# ETH-IO_RS485-DS18B20-Panel.net
KiCad netlist of a schematic drawn in EAGLE
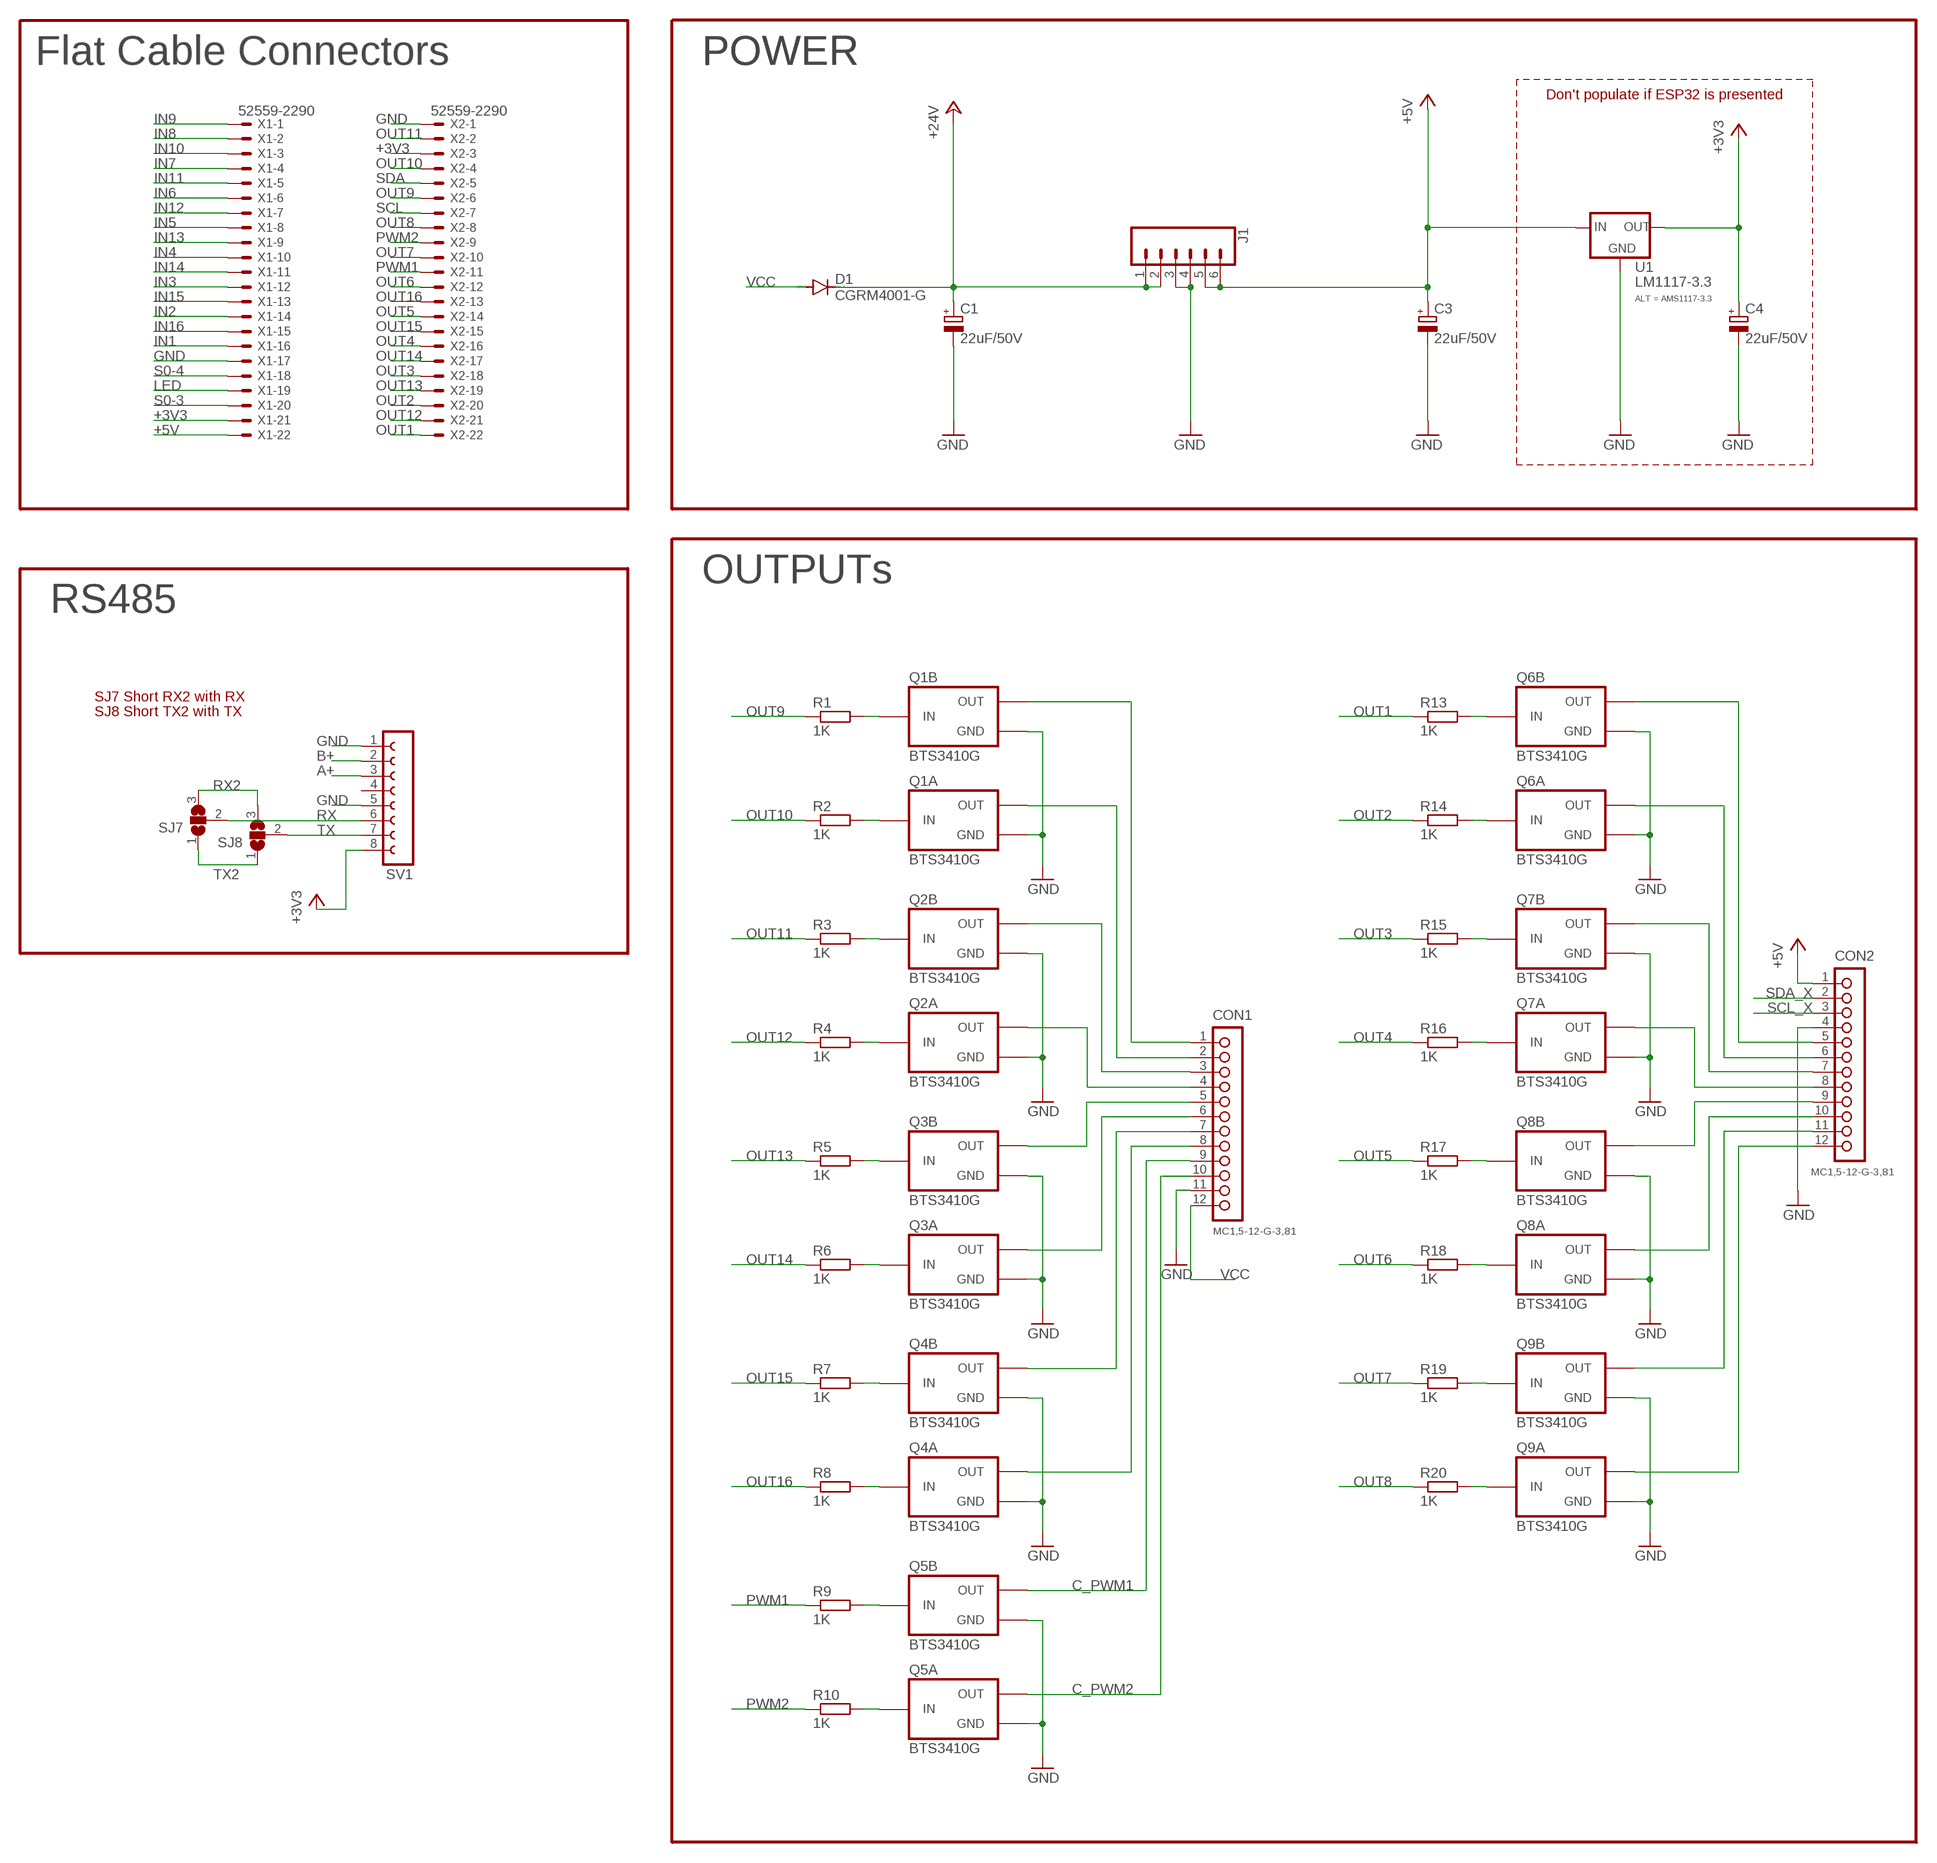
[diagram p0: schematic, sheet 1, part 1 of 2]
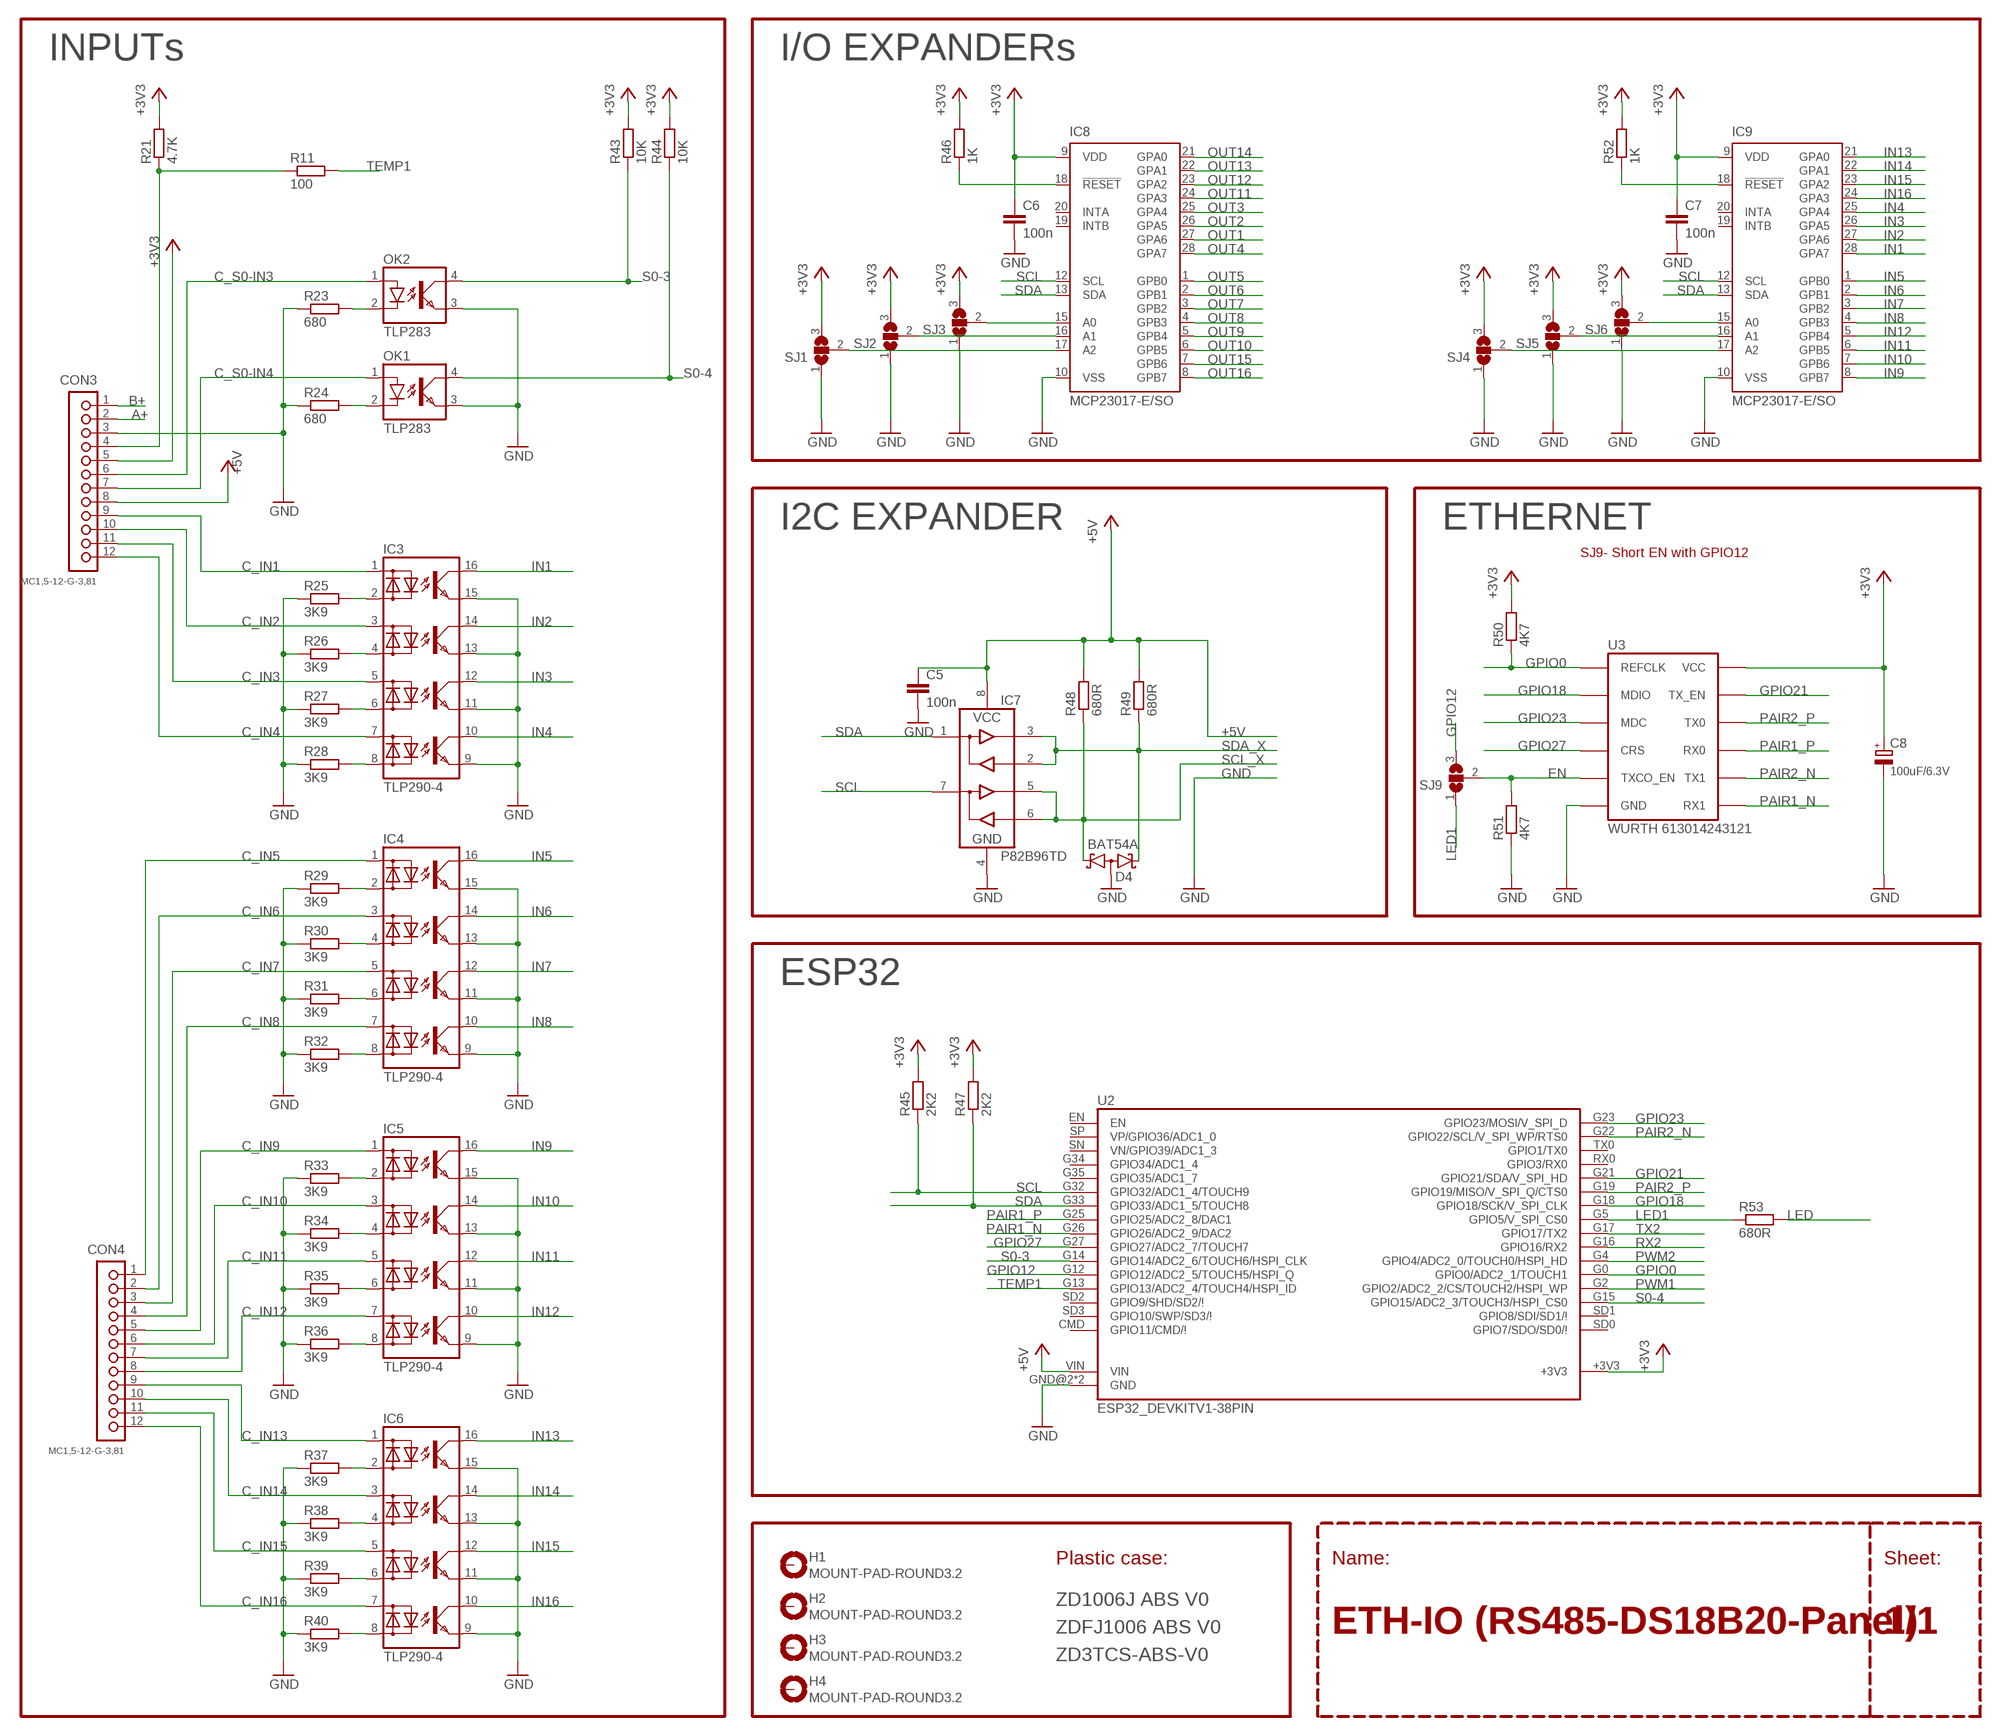
[diagram p1: schematic, sheet 1, part 2 of 2]

(export (version "E")
  (design (tool "Eeschema 10.0.6"))
  (components
    (comp (ref "C1")
      (value "22uF/50V")
      (footprint "eagle-import:PANASONIC_C")
      (libsource (lib "eagle-import") (part "CPOL-EUC"))
    )
    (comp (ref "C3")
      (value "22uF/50V")
      (footprint "eagle-import:PANASONIC_C")
      (libsource (lib "eagle-import") (part "CPOL-EUC"))
    )
    (comp (ref "C4")
      (value "22uF/50V")
      (footprint "eagle-import:PANASONIC_C")
      (libsource (lib "eagle-import") (part "CPOL-EUC"))
    )
    (comp (ref "C5")
      (value "100n")
      (footprint "eagle-import:C0805")
      (libsource (lib "eagle-import") (part "C-EUC0805"))
    )
    (comp (ref "C6")
      (value "100n")
      (footprint "eagle-import:C0805")
      (libsource (lib "eagle-import") (part "C-EUC0805"))
    )
    (comp (ref "C7")
      (value "100n")
      (footprint "eagle-import:C0805")
      (libsource (lib "eagle-import") (part "C-EUC0805"))
    )
    (comp (ref "C8")
      (value "100uF/6.3V")
      (footprint "eagle-import:PANASONIC_C")
      (libsource (lib "eagle-import") (part "CPOL-EUC"))
    )
    (comp (ref "CON1")
      (value "MC1,5-12-G-3,81")
      (footprint "eagle-import:MC1,5_12-G-3,81")
      (libsource (lib "eagle-import") (part "MC1,5-12-G-?3,81"))
    )
    (comp (ref "CON2")
      (value "MC1,5-12-G-3,81")
      (footprint "eagle-import:MC1,5_12-G-3,81")
      (libsource (lib "eagle-import") (part "MC1,5-12-G-?3,81"))
    )
    (comp (ref "CON3")
      (value "MC1,5-12-G-3,81")
      (footprint "eagle-import:MC1,5_12-G-3,81")
      (libsource (lib "eagle-import") (part "MC1,5-12-G-?3,81"))
    )
    (comp (ref "CON4")
      (value "MC1,5-12-G-3,81")
      (footprint "eagle-import:MC1,5_12-G-3,81")
      (libsource (lib "eagle-import") (part "MC1,5-12-G-?3,81"))
    )
    (comp (ref "D1")
      (value "CGRM4001-G")
      (footprint "eagle-import:SOD-123_MINI-SMA")
      (libsource (lib "eagle-import") (part "CGRM400-G1"))
    )
    (comp (ref "D4")
      (value "BAT54A")
      (footprint "eagle-import:SOT23")
      (libsource (lib "eagle-import") (part "BAT54A"))
    )
    (comp (ref "H1")
      (value "MOUNT-PAD-ROUND3.2")
      (footprint "eagle-import:3,2-PAD")
      (libsource (lib "eagle-import") (part "MOUNT-PAD-ROUND3.2"))
    )
    (comp (ref "H2")
      (value "MOUNT-PAD-ROUND3.2")
      (footprint "eagle-import:3,2-PAD")
      (libsource (lib "eagle-import") (part "MOUNT-PAD-ROUND3.2"))
    )
    (comp (ref "H3")
      (value "MOUNT-PAD-ROUND3.2")
      (footprint "eagle-import:3,2-PAD")
      (libsource (lib "eagle-import") (part "MOUNT-PAD-ROUND3.2"))
    )
    (comp (ref "H4")
      (value "MOUNT-PAD-ROUND3.2")
      (footprint "eagle-import:3,2-PAD")
      (libsource (lib "eagle-import") (part "MOUNT-PAD-ROUND3.2"))
    )
    (comp (ref "IC3")
      (value "TLP290-4")
      (footprint "eagle-import:SO16")
      (libsource (lib "eagle-import") (part "TLP290-4"))
    )
    (comp (ref "IC4")
      (value "TLP290-4")
      (footprint "eagle-import:SO16")
      (libsource (lib "eagle-import") (part "TLP290-4"))
    )
    (comp (ref "IC5")
      (value "TLP290-4")
      (footprint "eagle-import:SO16")
      (libsource (lib "eagle-import") (part "TLP290-4"))
    )
    (comp (ref "IC6")
      (value "TLP290-4")
      (footprint "eagle-import:SO16")
      (libsource (lib "eagle-import") (part "TLP290-4"))
    )
    (comp (ref "IC7")
      (value "P82B96TD")
      (footprint "eagle-import:SO08")
      (libsource (lib "eagle-import") (part "P82B96?TD"))
    )
    (comp (ref "IC8")
      (value "MCP23017-E/SO")
      (footprint "eagle-import:SO28W")
      (fields (field (name "MF") "MICROCHIP"))
      (libsource (lib "eagle-import") (part "MCP23017SO"))
    )
    (comp (ref "IC9")
      (value "MCP23017-E/SO")
      (footprint "eagle-import:SO28W")
      (fields (field (name "MF") "MICROCHIP"))
      (libsource (lib "eagle-import") (part "MCP23017SO"))
    )
    (comp (ref "J1")
      (value "CONN_06NO_SILK_FEMALE_PTH")
      (footprint "eagle-import:1X06_NO_SILK")
      (libsource (lib "eagle-import") (part "CONN_06NO_SILK_FEMALE_PTH"))
    )
    (comp (ref "OK1")
      (value "TLP283")
      (footprint "eagle-import:MINI-FLAT-4")
      (libsource (lib "eagle-import") (part "TLP283"))
    )
    (comp (ref "OK2")
      (value "TLP283")
      (footprint "eagle-import:MINI-FLAT-4")
      (libsource (lib "eagle-import") (part "TLP283"))
    )
    (comp (ref "Q1")
      (value "BTS3410G")
      (footprint "eagle-import:SO8")
      (libsource (lib "eagle-import") (part "BTS3410G"))
    )
    (comp (ref "Q2")
      (value "BTS3410G")
      (footprint "eagle-import:SO8")
      (libsource (lib "eagle-import") (part "BTS3410G"))
    )
    (comp (ref "Q3")
      (value "BTS3410G")
      (footprint "eagle-import:SO8")
      (libsource (lib "eagle-import") (part "BTS3410G"))
    )
    (comp (ref "Q4")
      (value "BTS3410G")
      (footprint "eagle-import:SO8")
      (libsource (lib "eagle-import") (part "BTS3410G"))
    )
    (comp (ref "Q5")
      (value "BTS3410G")
      (footprint "eagle-import:SO8")
      (libsource (lib "eagle-import") (part "BTS3410G"))
    )
    (comp (ref "Q6")
      (value "BTS3410G")
      (footprint "eagle-import:SO8")
      (libsource (lib "eagle-import") (part "BTS3410G"))
    )
    (comp (ref "Q7")
      (value "BTS3410G")
      (footprint "eagle-import:SO8")
      (libsource (lib "eagle-import") (part "BTS3410G"))
    )
    (comp (ref "Q8")
      (value "BTS3410G")
      (footprint "eagle-import:SO8")
      (libsource (lib "eagle-import") (part "BTS3410G"))
    )
    (comp (ref "Q9")
      (value "BTS3410G")
      (footprint "eagle-import:SO8")
      (libsource (lib "eagle-import") (part "BTS3410G"))
    )
    (comp (ref "R1")
      (value "1K")
      (footprint "eagle-import:R0805")
      (libsource (lib "eagle-import") (part "R-EU_R0805"))
    )
    (comp (ref "R2")
      (value "1K")
      (footprint "eagle-import:R0805")
      (libsource (lib "eagle-import") (part "R-EU_R0805"))
    )
    (comp (ref "R3")
      (value "1K")
      (footprint "eagle-import:R0805")
      (libsource (lib "eagle-import") (part "R-EU_R0805"))
    )
    (comp (ref "R4")
      (value "1K")
      (footprint "eagle-import:R0805")
      (libsource (lib "eagle-import") (part "R-EU_R0805"))
    )
    (comp (ref "R5")
      (value "1K")
      (footprint "eagle-import:R0805")
      (libsource (lib "eagle-import") (part "R-EU_R0805"))
    )
    (comp (ref "R6")
      (value "1K")
      (footprint "eagle-import:R0805")
      (libsource (lib "eagle-import") (part "R-EU_R0805"))
    )
    (comp (ref "R7")
      (value "1K")
      (footprint "eagle-import:R0805")
      (libsource (lib "eagle-import") (part "R-EU_R0805"))
    )
    (comp (ref "R8")
      (value "1K")
      (footprint "eagle-import:R0805")
      (libsource (lib "eagle-import") (part "R-EU_R0805"))
    )
    (comp (ref "R9")
      (value "1K")
      (footprint "eagle-import:R0805")
      (libsource (lib "eagle-import") (part "R-EU_R0805"))
    )
    (comp (ref "R10")
      (value "1K")
      (footprint "eagle-import:R0805")
      (libsource (lib "eagle-import") (part "R-EU_R0805"))
    )
    (comp (ref "R11")
      (value "100")
      (footprint "eagle-import:R0805")
      (libsource (lib "eagle-import") (part "R-EU_R0805"))
    )
    (comp (ref "R13")
      (value "1K")
      (footprint "eagle-import:R0805")
      (libsource (lib "eagle-import") (part "R-EU_R0805"))
    )
    (comp (ref "R14")
      (value "1K")
      (footprint "eagle-import:R0805")
      (libsource (lib "eagle-import") (part "R-EU_R0805"))
    )
    (comp (ref "R15")
      (value "1K")
      (footprint "eagle-import:R0805")
      (libsource (lib "eagle-import") (part "R-EU_R0805"))
    )
    (comp (ref "R16")
      (value "1K")
      (footprint "eagle-import:R0805")
      (libsource (lib "eagle-import") (part "R-EU_R0805"))
    )
    (comp (ref "R17")
      (value "1K")
      (footprint "eagle-import:R0805")
      (libsource (lib "eagle-import") (part "R-EU_R0805"))
    )
    (comp (ref "R18")
      (value "1K")
      (footprint "eagle-import:R0805")
      (libsource (lib "eagle-import") (part "R-EU_R0805"))
    )
    (comp (ref "R19")
      (value "1K")
      (footprint "eagle-import:R0805")
      (libsource (lib "eagle-import") (part "R-EU_R0805"))
    )
    (comp (ref "R20")
      (value "1K")
      (footprint "eagle-import:R0805")
      (libsource (lib "eagle-import") (part "R-EU_R0805"))
    )
    (comp (ref "R21")
      (value "4.7K")
      (footprint "eagle-import:R0805")
      (libsource (lib "eagle-import") (part "R-EU_R0805"))
    )
    (comp (ref "R23")
      (value "680")
      (footprint "eagle-import:R0805")
      (libsource (lib "eagle-import") (part "R-EU_R0805"))
    )
    (comp (ref "R24")
      (value "680")
      (footprint "eagle-import:R0805")
      (libsource (lib "eagle-import") (part "R-EU_R0805"))
    )
    (comp (ref "R25")
      (value "3K9")
      (footprint "eagle-import:R0805")
      (libsource (lib "eagle-import") (part "R-EU_R0805"))
    )
    (comp (ref "R26")
      (value "3K9")
      (footprint "eagle-import:R0805")
      (libsource (lib "eagle-import") (part "R-EU_R0805"))
    )
    (comp (ref "R27")
      (value "3K9")
      (footprint "eagle-import:R0805")
      (libsource (lib "eagle-import") (part "R-EU_R0805"))
    )
    (comp (ref "R28")
      (value "3K9")
      (footprint "eagle-import:R0805")
      (libsource (lib "eagle-import") (part "R-EU_R0805"))
    )
    (comp (ref "R29")
      (value "3K9")
      (footprint "eagle-import:R0805")
      (libsource (lib "eagle-import") (part "R-EU_R0805"))
    )
    (comp (ref "R30")
      (value "3K9")
      (footprint "eagle-import:R0805")
      (libsource (lib "eagle-import") (part "R-EU_R0805"))
    )
    (comp (ref "R31")
      (value "3K9")
      (footprint "eagle-import:R0805")
      (libsource (lib "eagle-import") (part "R-EU_R0805"))
    )
    (comp (ref "R32")
      (value "3K9")
      (footprint "eagle-import:R0805")
      (libsource (lib "eagle-import") (part "R-EU_R0805"))
    )
    (comp (ref "R33")
      (value "3K9")
      (footprint "eagle-import:R0805")
      (libsource (lib "eagle-import") (part "R-EU_R0805"))
    )
    (comp (ref "R34")
      (value "3K9")
      (footprint "eagle-import:R0805")
      (libsource (lib "eagle-import") (part "R-EU_R0805"))
    )
    (comp (ref "R35")
      (value "3K9")
      (footprint "eagle-import:R0805")
      (libsource (lib "eagle-import") (part "R-EU_R0805"))
    )
    (comp (ref "R36")
      (value "3K9")
      (footprint "eagle-import:R0805")
      (libsource (lib "eagle-import") (part "R-EU_R0805"))
    )
    (comp (ref "R37")
      (value "3K9")
      (footprint "eagle-import:R0805")
      (libsource (lib "eagle-import") (part "R-EU_R0805"))
    )
    (comp (ref "R38")
      (value "3K9")
      (footprint "eagle-import:R0805")
      (libsource (lib "eagle-import") (part "R-EU_R0805"))
    )
    (comp (ref "R39")
      (value "3K9")
      (footprint "eagle-import:R0805")
      (libsource (lib "eagle-import") (part "R-EU_R0805"))
    )
    (comp (ref "R40")
      (value "3K9")
      (footprint "eagle-import:R0805")
      (libsource (lib "eagle-import") (part "R-EU_R0805"))
    )
    (comp (ref "R43")
      (value "10K")
      (footprint "eagle-import:R0805")
      (libsource (lib "eagle-import") (part "R-EU_R0805"))
    )
    (comp (ref "R44")
      (value "10K")
      (footprint "eagle-import:R0805")
      (libsource (lib "eagle-import") (part "R-EU_R0805"))
    )
    (comp (ref "R45")
      (value "2K2")
      (footprint "eagle-import:R0805")
      (libsource (lib "eagle-import") (part "R-EU_R0805"))
    )
    (comp (ref "R46")
      (value "1K")
      (footprint "eagle-import:R0805")
      (libsource (lib "eagle-import") (part "R-EU_R0805"))
    )
    (comp (ref "R47")
      (value "2K2")
      (footprint "eagle-import:R0805")
      (libsource (lib "eagle-import") (part "R-EU_R0805"))
    )
    (comp (ref "R48")
      (value "680R")
      (footprint "eagle-import:R0805")
      (libsource (lib "eagle-import") (part "R-EU_R0805"))
    )
    (comp (ref "R49")
      (value "680R")
      (footprint "eagle-import:R0805")
      (libsource (lib "eagle-import") (part "R-EU_R0805"))
    )
    (comp (ref "R50")
      (value "4K7")
      (footprint "eagle-import:R0805")
      (libsource (lib "eagle-import") (part "R-EU_R0805"))
    )
    (comp (ref "R51")
      (value "4K7")
      (footprint "eagle-import:R0805")
      (libsource (lib "eagle-import") (part "R-EU_R0805"))
    )
    (comp (ref "R52")
      (value "1K")
      (footprint "eagle-import:R0805")
      (libsource (lib "eagle-import") (part "R-EU_R0805"))
    )
    (comp (ref "R53")
      (value "680R")
      (footprint "eagle-import:R0805")
      (libsource (lib "eagle-import") (part "R-EU_R0805"))
    )
    (comp (ref "SJ1")
      (value "SJ2W")
      (footprint "eagle-import:SJ_2")
      (libsource (lib "eagle-import") (part "SJ2W"))
    )
    (comp (ref "SJ2")
      (value "SJ2W")
      (footprint "eagle-import:SJ_2")
      (libsource (lib "eagle-import") (part "SJ2W"))
    )
    (comp (ref "SJ3")
      (value "SJ2W")
      (footprint "eagle-import:SJ_2")
      (libsource (lib "eagle-import") (part "SJ2W"))
    )
    (comp (ref "SJ4")
      (value "SJ2W")
      (footprint "eagle-import:SJ_2")
      (libsource (lib "eagle-import") (part "SJ2W"))
    )
    (comp (ref "SJ5")
      (value "SJ2W")
      (footprint "eagle-import:SJ_2")
      (libsource (lib "eagle-import") (part "SJ2W"))
    )
    (comp (ref "SJ6")
      (value "SJ2W")
      (footprint "eagle-import:SJ_2")
      (libsource (lib "eagle-import") (part "SJ2W"))
    )
    (comp (ref "SJ7")
      (value "SJ2W")
      (footprint "eagle-import:SJ_2")
      (libsource (lib "eagle-import") (part "SJ2W"))
    )
    (comp (ref "SJ8")
      (value "SJ2W")
      (footprint "eagle-import:SJ_2")
      (libsource (lib "eagle-import") (part "SJ2W"))
    )
    (comp (ref "SJ9")
      (value "SJ2W")
      (footprint "eagle-import:SJ_2")
      (libsource (lib "eagle-import") (part "SJ2W"))
    )
    (comp (ref "SV1")
      (value "FE08-1")
      (footprint "eagle-import:FE08")
      (libsource (lib "eagle-import") (part "FE08-1"))
    )
    (comp (ref "U1")
      (value "LM1117-3.3")
      (footprint "eagle-import:SOT223")
      (fields (field (name "ALT") "AMS1117-3.3"))
      (libsource (lib "eagle-import") (part "LM1117-3.3"))
    )
    (comp (ref "U2")
      (value "ESP32_DEVKITV1-38PIN")
      (footprint "eagle-import:ESP32_DEVKITV1_38PIN")
      (libsource (lib "eagle-import") (part "ESP32_DEVKITV1-38PIN"))
    )
    (comp (ref "U3")
      (value "WURTH 613014243121")
      (footprint "eagle-import:LAN8720_ETH_BOARD")
      (libsource (lib "eagle-import") (part "LAN8720_ETH_BOARD"))
    )
    (comp (ref "X1")
      (value "52559-2290")
      (footprint "eagle-import:52559-2290")
      (fields (field (name "MF") "MOLEX"))
      (libsource (lib "eagle-import") (part "52559-2290"))
    )
    (comp (ref "X2")
      (value "52559-2290")
      (footprint "eagle-import:52559-2290")
      (fields (field (name "MF") "MOLEX"))
      (libsource (lib "eagle-import") (part "52559-2290"))
    )
  )
  (nets
    (net (code "1") (name "+3V3") (class "Default")
      (node (ref "C4") (pin "+") (pinfunction "+_+") (pintype "passive"))
      (node (ref "C6") (pin "1") (pinfunction "1_1") (pintype "passive"))
      (node (ref "C7") (pin "1") (pinfunction "1_1") (pintype "passive"))
      (node (ref "C8") (pin "+") (pinfunction "+_+") (pintype "passive"))
      (node (ref "CON3") (pin "5") (pinfunction "5_5") (pintype "passive"))
      (node (ref "IC8") (pin "9") (pinfunction "VDD_9") (pintype "power_in"))
      (node (ref "IC9") (pin "9") (pinfunction "VDD_9") (pintype "power_in"))
      (node (ref "R21") (pin "2") (pinfunction "2_2") (pintype "passive"))
      (node (ref "R43") (pin "2") (pinfunction "2_2") (pintype "passive"))
      (node (ref "R44") (pin "2") (pinfunction "2_2") (pintype "passive"))
      (node (ref "R45") (pin "2") (pinfunction "2_2") (pintype "passive"))
      (node (ref "R46") (pin "2") (pinfunction "2_2") (pintype "passive"))
      (node (ref "R47") (pin "2") (pinfunction "2_2") (pintype "passive"))
      (node (ref "R50") (pin "2") (pinfunction "2_2") (pintype "passive"))
      (node (ref "R52") (pin "2") (pinfunction "2_2") (pintype "passive"))
      (node (ref "SJ1") (pin "3") (pinfunction "3_3") (pintype "passive"))
      (node (ref "SJ2") (pin "3") (pinfunction "3_3") (pintype "passive"))
      (node (ref "SJ3") (pin "3") (pinfunction "3_3") (pintype "passive"))
      (node (ref "SJ4") (pin "3") (pinfunction "3_3") (pintype "passive"))
      (node (ref "SJ5") (pin "3") (pinfunction "3_3") (pintype "passive"))
      (node (ref "SJ6") (pin "3") (pinfunction "3_3") (pintype "passive"))
      (node (ref "SV1") (pin "8") (pinfunction "8_8") (pintype "passive"))
      (node (ref "U1") (pin "2") (pinfunction "OUT_2") (pintype "output"))
      (node (ref "U1") (pin "4") (pinfunction "OUT_4") (pintype "output"))
      (node (ref "U2") (pin "+3V3") (pinfunction "+3V3_+3V3") (pintype "power_in"))
      (node (ref "U3") (pin "VCC") (pinfunction "VCC_VCC") (pintype "power_in"))
      (node (ref "U3") (pin "VCC@1") (pinfunction "VCC_VCC@1") (pintype "power_in"))
      (node (ref "X1") (pin "21") (pinfunction "S_21") (pintype "passive"))
      (node (ref "X2") (pin "3") (pinfunction "S_3") (pintype "passive"))
    )
    (net (code "2") (name "+5V") (class "Default")
      (node (ref "C3") (pin "+") (pinfunction "+_+") (pintype "passive"))
      (node (ref "C5") (pin "1") (pinfunction "1_1") (pintype "passive"))
      (node (ref "CON2") (pin "1") (pinfunction "1_1") (pintype "passive"))
      (node (ref "CON3") (pin "8") (pinfunction "8_8") (pintype "passive"))
      (node (ref "IC7") (pin "8") (pinfunction "VCC_8") (pintype "power_in"))
      (node (ref "J1") (pin "5") (pinfunction "5_5") (pintype "passive"))
      (node (ref "J1") (pin "6") (pinfunction "6_6") (pintype "passive"))
      (node (ref "R48") (pin "2") (pinfunction "2_2") (pintype "passive"))
      (node (ref "R49") (pin "2") (pinfunction "2_2") (pintype "passive"))
      (node (ref "U1") (pin "3") (pinfunction "IN_3") (pintype "input"))
      (node (ref "U2") (pin "VIN") (pinfunction "VIN_VIN") (pintype "power_in"))
      (node (ref "X1") (pin "22") (pinfunction "S_22") (pintype "passive"))
    )
    (net (code "3") (name "+24V") (class "Default")
      (node (ref "C1") (pin "+") (pinfunction "+_+") (pintype "passive"))
      (node (ref "D1") (pin "C") (pinfunction "C_C") (pintype "passive"))
      (node (ref "J1") (pin "1") (pinfunction "1_1") (pintype "passive"))
      (node (ref "J1") (pin "2") (pinfunction "2_2") (pintype "passive"))
    )
    (net (code "4") (name "/A+") (class "Default")
      (node (ref "CON3") (pin "2") (pinfunction "2_2") (pintype "passive"))
      (node (ref "SV1") (pin "3") (pinfunction "3_3") (pintype "passive"))
    )
    (net (code "5") (name "/B+") (class "Default")
      (node (ref "CON3") (pin "1") (pinfunction "1_1") (pintype "passive"))
      (node (ref "SV1") (pin "2") (pinfunction "2_2") (pintype "passive"))
    )
    (net (code "6") (name "/C_IN1") (class "Default")
      (node (ref "CON3") (pin "9") (pinfunction "9_9") (pintype "passive"))
      (node (ref "IC3") (pin "1") (pinfunction "A1_1") (pintype "passive"))
    )
    (net (code "7") (name "/C_IN2") (class "Default")
      (node (ref "CON3") (pin "10") (pinfunction "10_10") (pintype "passive"))
      (node (ref "IC3") (pin "3") (pinfunction "A2_3") (pintype "passive"))
    )
    (net (code "8") (name "/C_IN3") (class "Default")
      (node (ref "CON3") (pin "11") (pinfunction "11_11") (pintype "passive"))
      (node (ref "IC3") (pin "5") (pinfunction "A3_5") (pintype "passive"))
    )
    (net (code "9") (name "/C_IN4") (class "Default")
      (node (ref "CON3") (pin "12") (pinfunction "12_12") (pintype "passive"))
      (node (ref "IC3") (pin "7") (pinfunction "A4_7") (pintype "passive"))
    )
    (net (code "10") (name "/C_IN5") (class "Default")
      (node (ref "CON4") (pin "1") (pinfunction "1_1") (pintype "passive"))
      (node (ref "IC4") (pin "1") (pinfunction "A1_1") (pintype "passive"))
    )
    (net (code "11") (name "/C_IN6") (class "Default")
      (node (ref "CON4") (pin "2") (pinfunction "2_2") (pintype "passive"))
      (node (ref "IC4") (pin "3") (pinfunction "A2_3") (pintype "passive"))
    )
    (net (code "12") (name "/C_IN7") (class "Default")
      (node (ref "CON4") (pin "3") (pinfunction "3_3") (pintype "passive"))
      (node (ref "IC4") (pin "5") (pinfunction "A3_5") (pintype "passive"))
    )
    (net (code "13") (name "/C_IN8") (class "Default")
      (node (ref "CON4") (pin "4") (pinfunction "4_4") (pintype "passive"))
      (node (ref "IC4") (pin "7") (pinfunction "A4_7") (pintype "passive"))
    )
    (net (code "14") (name "/C_IN9") (class "Default")
      (node (ref "CON4") (pin "5") (pinfunction "5_5") (pintype "passive"))
      (node (ref "IC5") (pin "1") (pinfunction "A1_1") (pintype "passive"))
    )
    (net (code "15") (name "/C_IN10") (class "Default")
      (node (ref "CON4") (pin "6") (pinfunction "6_6") (pintype "passive"))
      (node (ref "IC5") (pin "3") (pinfunction "A2_3") (pintype "passive"))
    )
    (net (code "16") (name "/C_IN11") (class "Default")
      (node (ref "CON4") (pin "7") (pinfunction "7_7") (pintype "passive"))
      (node (ref "IC5") (pin "5") (pinfunction "A3_5") (pintype "passive"))
    )
    (net (code "17") (name "/C_IN12") (class "Default")
      (node (ref "CON4") (pin "8") (pinfunction "8_8") (pintype "passive"))
      (node (ref "IC5") (pin "7") (pinfunction "A4_7") (pintype "passive"))
    )
    (net (code "18") (name "/C_IN13") (class "Default")
      (node (ref "CON4") (pin "9") (pinfunction "9_9") (pintype "passive"))
      (node (ref "IC6") (pin "1") (pinfunction "A1_1") (pintype "passive"))
    )
    (net (code "19") (name "/C_IN14") (class "Default")
      (node (ref "CON4") (pin "10") (pinfunction "10_10") (pintype "passive"))
      (node (ref "IC6") (pin "3") (pinfunction "A2_3") (pintype "passive"))
    )
    (net (code "20") (name "/C_IN15") (class "Default")
      (node (ref "CON4") (pin "11") (pinfunction "11_11") (pintype "passive"))
      (node (ref "IC6") (pin "5") (pinfunction "A3_5") (pintype "passive"))
    )
    (net (code "21") (name "/C_IN16") (class "Default")
      (node (ref "CON4") (pin "12") (pinfunction "12_12") (pintype "passive"))
      (node (ref "IC6") (pin "7") (pinfunction "A4_7") (pintype "passive"))
    )
    (net (code "22") (name "/C_PWM1") (class "Default")
      (node (ref "CON1") (pin "9") (pinfunction "9_9") (pintype "passive"))
      (node (ref "Q5") (pin "5") (pinfunction "OUT_5") (pintype "output"))
      (node (ref "Q5") (pin "6") (pinfunction "OUT_6") (pintype "output"))
    )
    (net (code "23") (name "/C_PWM2") (class "Default")
      (node (ref "CON1") (pin "10") (pinfunction "10_10") (pintype "passive"))
      (node (ref "Q5") (pin "7") (pinfunction "OUT_7") (pintype "output"))
      (node (ref "Q5") (pin "8") (pinfunction "OUT_8") (pintype "output"))
    )
    (net (code "24") (name "/C_S0-IN3") (class "Default")
      (node (ref "CON3") (pin "6") (pinfunction "6_6") (pintype "passive"))
      (node (ref "OK2") (pin "1") (pinfunction "A_1") (pintype "passive"))
    )
    (net (code "25") (name "/C_S0-IN4") (class "Default")
      (node (ref "CON3") (pin "7") (pinfunction "7_7") (pintype "passive"))
      (node (ref "OK1") (pin "1") (pinfunction "A_1") (pintype "passive"))
    )
    (net (code "26") (name "/EN") (class "Default")
      (node (ref "R51") (pin "2") (pinfunction "2_2") (pintype "passive"))
      (node (ref "SJ9") (pin "2") (pinfunction "2_2") (pintype "passive"))
      (node (ref "U3") (pin "TXCO_EN") (pinfunction "TXCO_EN_TXCO_EN") (pintype "input"))
    )
    (net (code "27") (name "/GPIO0") (class "Default")
      (node (ref "R50") (pin "1") (pinfunction "1_1") (pintype "passive"))
      (node (ref "U2") (pin "G0") (pinfunction "GPIO0/ADC2_1/TOUCH1_G0") (pintype "bidirectional"))
      (node (ref "U3") (pin "INT") (pinfunction "REFCLK_INT") (pintype "output"))
    )
    (net (code "28") (name "/GPIO12") (class "Default")
      (node (ref "SJ9") (pin "3") (pinfunction "3_3") (pintype "passive"))
      (node (ref "U2") (pin "G12") (pinfunction "GPIO12/ADC2_5/TOUCH5/HSPI_Q_G12") (pintype "bidirectional"))
    )
    (net (code "29") (name "/GPIO18") (class "Default")
      (node (ref "U2") (pin "G18") (pinfunction "GPIO18/SCK/V_SPI_CLK_G18") (pintype "bidirectional"))
      (node (ref "U3") (pin "MDIO") (pinfunction "MDIO_MDIO") (pintype "bidirectional"))
    )
    (net (code "30") (name "/GPIO21") (class "Default")
      (node (ref "U2") (pin "G21") (pinfunction "GPIO21/SDA/V_SPI_HD_G21") (pintype "bidirectional"))
      (node (ref "U3") (pin "TX_EN") (pinfunction "TX_EN_TX_EN") (pintype "input"))
    )
    (net (code "31") (name "/GPIO23") (class "Default")
      (node (ref "U2") (pin "G23") (pinfunction "GPIO23/MOSI/V_SPI_D_G23") (pintype "bidirectional"))
      (node (ref "U3") (pin "MDC") (pinfunction "MDC_MDC") (pintype "bidirectional"))
    )
    (net (code "32") (name "/GPIO27") (class "Default")
      (node (ref "U2") (pin "G27") (pinfunction "GPIO27/ADC2_7/TOUCH7_G27") (pintype "bidirectional"))
      (node (ref "U3") (pin "CRS") (pinfunction "CRS_CRS") (pintype "bidirectional"))
    )
    (net (code "33") (name "/IN1") (class "Default")
      (node (ref "IC3") (pin "16") (pinfunction "COL1_16") (pintype "passive"))
      (node (ref "IC9") (pin "28") (pinfunction "GPA7_28") (pintype "bidirectional"))
      (node (ref "X1") (pin "16") (pinfunction "S_16") (pintype "passive"))
    )
    (net (code "34") (name "/IN2") (class "Default")
      (node (ref "IC3") (pin "14") (pinfunction "COL2_14") (pintype "passive"))
      (node (ref "IC9") (pin "27") (pinfunction "GPA6_27") (pintype "bidirectional"))
      (node (ref "X1") (pin "14") (pinfunction "S_14") (pintype "passive"))
    )
    (net (code "35") (name "/IN3") (class "Default")
      (node (ref "IC3") (pin "12") (pinfunction "COL3_12") (pintype "passive"))
      (node (ref "IC9") (pin "26") (pinfunction "GPA5_26") (pintype "bidirectional"))
      (node (ref "X1") (pin "12") (pinfunction "S_12") (pintype "passive"))
    )
    (net (code "36") (name "/IN4") (class "Default")
      (node (ref "IC3") (pin "10") (pinfunction "COL4_10") (pintype "passive"))
      (node (ref "IC9") (pin "25") (pinfunction "GPA4_25") (pintype "bidirectional"))
      (node (ref "X1") (pin "10") (pinfunction "S_10") (pintype "passive"))
    )
    (net (code "37") (name "/IN5") (class "Default")
      (node (ref "IC4") (pin "16") (pinfunction "COL1_16") (pintype "passive"))
      (node (ref "IC9") (pin "1") (pinfunction "GPB0_1") (pintype "bidirectional"))
      (node (ref "X1") (pin "8") (pinfunction "S_8") (pintype "passive"))
    )
    (net (code "38") (name "/IN6") (class "Default")
      (node (ref "IC4") (pin "14") (pinfunction "COL2_14") (pintype "passive"))
      (node (ref "IC9") (pin "2") (pinfunction "GPB1_2") (pintype "bidirectional"))
      (node (ref "X1") (pin "6") (pinfunction "S_6") (pintype "passive"))
    )
    (net (code "39") (name "/IN7") (class "Default")
      (node (ref "IC4") (pin "12") (pinfunction "COL3_12") (pintype "passive"))
      (node (ref "IC9") (pin "3") (pinfunction "GPB2_3") (pintype "bidirectional"))
      (node (ref "X1") (pin "4") (pinfunction "S_4") (pintype "passive"))
    )
    (net (code "40") (name "/IN8") (class "Default")
      (node (ref "IC4") (pin "10") (pinfunction "COL4_10") (pintype "passive"))
      (node (ref "IC9") (pin "4") (pinfunction "GPB3_4") (pintype "bidirectional"))
      (node (ref "X1") (pin "2") (pinfunction "S_2") (pintype "passive"))
    )
    (net (code "41") (name "/IN9") (class "Default")
      (node (ref "IC5") (pin "16") (pinfunction "COL1_16") (pintype "passive"))
      (node (ref "IC9") (pin "8") (pinfunction "GPB7_8") (pintype "bidirectional"))
      (node (ref "X1") (pin "1") (pinfunction "S_1") (pintype "passive"))
    )
    (net (code "42") (name "/IN10") (class "Default")
      (node (ref "IC5") (pin "14") (pinfunction "COL2_14") (pintype "passive"))
      (node (ref "IC9") (pin "7") (pinfunction "GPB6_7") (pintype "bidirectional"))
      (node (ref "X1") (pin "3") (pinfunction "S_3") (pintype "passive"))
    )
    (net (code "43") (name "/IN11") (class "Default")
      (node (ref "IC5") (pin "12") (pinfunction "COL3_12") (pintype "passive"))
      (node (ref "IC9") (pin "6") (pinfunction "GPB5_6") (pintype "bidirectional"))
      (node (ref "X1") (pin "5") (pinfunction "S_5") (pintype "passive"))
    )
    (net (code "44") (name "/IN12") (class "Default")
      (node (ref "IC5") (pin "10") (pinfunction "COL4_10") (pintype "passive"))
      (node (ref "IC9") (pin "5") (pinfunction "GPB4_5") (pintype "bidirectional"))
      (node (ref "X1") (pin "7") (pinfunction "S_7") (pintype "passive"))
    )
    (net (code "45") (name "/IN13") (class "Default")
      (node (ref "IC6") (pin "16") (pinfunction "COL1_16") (pintype "passive"))
      (node (ref "IC9") (pin "21") (pinfunction "GPA0_21") (pintype "bidirectional"))
      (node (ref "X1") (pin "9") (pinfunction "S_9") (pintype "passive"))
    )
    (net (code "46") (name "/IN14") (class "Default")
      (node (ref "IC6") (pin "14") (pinfunction "COL2_14") (pintype "passive"))
      (node (ref "IC9") (pin "22") (pinfunction "GPA1_22") (pintype "bidirectional"))
      (node (ref "X1") (pin "11") (pinfunction "S_11") (pintype "passive"))
    )
    (net (code "47") (name "/IN15") (class "Default")
      (node (ref "IC6") (pin "12") (pinfunction "COL3_12") (pintype "passive"))
      (node (ref "IC9") (pin "23") (pinfunction "GPA2_23") (pintype "bidirectional"))
      (node (ref "X1") (pin "13") (pinfunction "S_13") (pintype "passive"))
    )
    (net (code "48") (name "/IN16") (class "Default")
      (node (ref "IC6") (pin "10") (pinfunction "COL4_10") (pintype "passive"))
      (node (ref "IC9") (pin "24") (pinfunction "GPA3_24") (pintype "bidirectional"))
      (node (ref "X1") (pin "15") (pinfunction "S_15") (pintype "passive"))
    )
    (net (code "49") (name "/LED") (class "Default")
      (node (ref "R53") (pin "2") (pinfunction "2_2") (pintype "passive"))
      (node (ref "X1") (pin "19") (pinfunction "S_19") (pintype "passive"))
    )
    (net (code "50") (name "/LED1") (class "Default")
      (node (ref "R53") (pin "1") (pinfunction "1_1") (pintype "passive"))
      (node (ref "SJ9") (pin "1") (pinfunction "1_1") (pintype "passive"))
      (node (ref "U2") (pin "G5") (pinfunction "GPIO5/V_SPI_CS0_G5") (pintype "bidirectional"))
    )
    (net (code "51") (name "/OUT1") (class "Default")
      (node (ref "IC8") (pin "27") (pinfunction "GPA6_27") (pintype "bidirectional"))
      (node (ref "R13") (pin "1") (pinfunction "1_1") (pintype "passive"))
      (node (ref "X2") (pin "22") (pinfunction "S_22") (pintype "passive"))
    )
    (net (code "52") (name "/OUT2") (class "Default")
      (node (ref "IC8") (pin "26") (pinfunction "GPA5_26") (pintype "bidirectional"))
      (node (ref "R14") (pin "1") (pinfunction "1_1") (pintype "passive"))
      (node (ref "X2") (pin "20") (pinfunction "S_20") (pintype "passive"))
    )
    (net (code "53") (name "/OUT3") (class "Default")
      (node (ref "IC8") (pin "25") (pinfunction "GPA4_25") (pintype "bidirectional"))
      (node (ref "R15") (pin "1") (pinfunction "1_1") (pintype "passive"))
      (node (ref "X2") (pin "18") (pinfunction "S_18") (pintype "passive"))
    )
    (net (code "54") (name "/OUT4") (class "Default")
      (node (ref "IC8") (pin "28") (pinfunction "GPA7_28") (pintype "bidirectional"))
      (node (ref "R16") (pin "1") (pinfunction "1_1") (pintype "passive"))
      (node (ref "X2") (pin "16") (pinfunction "S_16") (pintype "passive"))
    )
    (net (code "55") (name "/OUT5") (class "Default")
      (node (ref "IC8") (pin "1") (pinfunction "GPB0_1") (pintype "bidirectional"))
      (node (ref "R17") (pin "1") (pinfunction "1_1") (pintype "passive"))
      (node (ref "X2") (pin "14") (pinfunction "S_14") (pintype "passive"))
    )
    (net (code "56") (name "/OUT6") (class "Default")
      (node (ref "IC8") (pin "2") (pinfunction "GPB1_2") (pintype "bidirectional"))
      (node (ref "R18") (pin "1") (pinfunction "1_1") (pintype "passive"))
      (node (ref "X2") (pin "12") (pinfunction "S_12") (pintype "passive"))
    )
    (net (code "57") (name "/OUT7") (class "Default")
      (node (ref "IC8") (pin "3") (pinfunction "GPB2_3") (pintype "bidirectional"))
      (node (ref "R19") (pin "1") (pinfunction "1_1") (pintype "passive"))
      (node (ref "X2") (pin "10") (pinfunction "S_10") (pintype "passive"))
    )
    (net (code "58") (name "/OUT8") (class "Default")
      (node (ref "IC8") (pin "4") (pinfunction "GPB3_4") (pintype "bidirectional"))
      (node (ref "R20") (pin "1") (pinfunction "1_1") (pintype "passive"))
      (node (ref "X2") (pin "8") (pinfunction "S_8") (pintype "passive"))
    )
    (net (code "59") (name "/OUT9") (class "Default")
      (node (ref "IC8") (pin "5") (pinfunction "GPB4_5") (pintype "bidirectional"))
      (node (ref "R1") (pin "1") (pinfunction "1_1") (pintype "passive"))
      (node (ref "X2") (pin "6") (pinfunction "S_6") (pintype "passive"))
    )
    (net (code "60") (name "/OUT10") (class "Default")
      (node (ref "IC8") (pin "6") (pinfunction "GPB5_6") (pintype "bidirectional"))
      (node (ref "R2") (pin "1") (pinfunction "1_1") (pintype "passive"))
      (node (ref "X2") (pin "4") (pinfunction "S_4") (pintype "passive"))
    )
    (net (code "61") (name "/OUT11") (class "Default")
      (node (ref "IC8") (pin "24") (pinfunction "GPA3_24") (pintype "bidirectional"))
      (node (ref "R3") (pin "1") (pinfunction "1_1") (pintype "passive"))
      (node (ref "X2") (pin "2") (pinfunction "S_2") (pintype "passive"))
    )
    (net (code "62") (name "/OUT12") (class "Default")
      (node (ref "IC8") (pin "23") (pinfunction "GPA2_23") (pintype "bidirectional"))
      (node (ref "R4") (pin "1") (pinfunction "1_1") (pintype "passive"))
      (node (ref "X2") (pin "21") (pinfunction "S_21") (pintype "passive"))
    )
    (net (code "63") (name "/OUT13") (class "Default")
      (node (ref "IC8") (pin "22") (pinfunction "GPA1_22") (pintype "bidirectional"))
      (node (ref "R5") (pin "1") (pinfunction "1_1") (pintype "passive"))
      (node (ref "X2") (pin "19") (pinfunction "S_19") (pintype "passive"))
    )
    (net (code "64") (name "/OUT14") (class "Default")
      (node (ref "IC8") (pin "21") (pinfunction "GPA0_21") (pintype "bidirectional"))
      (node (ref "R6") (pin "1") (pinfunction "1_1") (pintype "passive"))
      (node (ref "X2") (pin "17") (pinfunction "S_17") (pintype "passive"))
    )
    (net (code "65") (name "/OUT15") (class "Default")
      (node (ref "IC8") (pin "7") (pinfunction "GPB6_7") (pintype "bidirectional"))
      (node (ref "R7") (pin "1") (pinfunction "1_1") (pintype "passive"))
      (node (ref "X2") (pin "15") (pinfunction "S_15") (pintype "passive"))
    )
    (net (code "66") (name "/OUT16") (class "Default")
      (node (ref "IC8") (pin "8") (pinfunction "GPB7_8") (pintype "bidirectional"))
      (node (ref "R8") (pin "1") (pinfunction "1_1") (pintype "passive"))
      (node (ref "X2") (pin "13") (pinfunction "S_13") (pintype "passive"))
    )
    (net (code "67") (name "/PAIR1_N") (class "Default")
      (node (ref "U2") (pin "G26") (pinfunction "GPIO26/ADC2_9/DAC2_G26") (pintype "bidirectional"))
      (node (ref "U3") (pin "RX1") (pinfunction "RX1_RX1") (pintype "input"))
    )
    (net (code "68") (name "/PAIR1_P") (class "Default")
      (node (ref "U2") (pin "G25") (pinfunction "GPIO25/ADC2_8/DAC1_G25") (pintype "bidirectional"))
      (node (ref "U3") (pin "RX0") (pinfunction "RX0_RX0") (pintype "input"))
    )
    (net (code "69") (name "/PAIR2_N") (class "Default")
      (node (ref "U2") (pin "G22") (pinfunction "GPIO22/SCL/V_SPI_WP/RTS0_G22") (pintype "bidirectional"))
      (node (ref "U3") (pin "TX1") (pinfunction "TX1_TX1") (pintype "output"))
    )
    (net (code "70") (name "/PAIR2_P") (class "Default")
      (node (ref "U2") (pin "G19") (pinfunction "GPIO19/MISO/V_SPI_Q/CTS0_G19") (pintype "bidirectional"))
      (node (ref "U3") (pin "TX0") (pinfunction "TX0_TX0") (pintype "output"))
    )
    (net (code "71") (name "/PWM1") (class "Default")
      (node (ref "R9") (pin "1") (pinfunction "1_1") (pintype "passive"))
      (node (ref "U2") (pin "G2") (pinfunction "GPIO2/ADC2_2/CS/TOUCH2/HSPI_WP_G2") (pintype "bidirectional"))
      (node (ref "X2") (pin "11") (pinfunction "S_11") (pintype "passive"))
    )
    (net (code "72") (name "/PWM2") (class "Default")
      (node (ref "R10") (pin "1") (pinfunction "1_1") (pintype "passive"))
      (node (ref "U2") (pin "G4") (pinfunction "GPIO4/ADC2_0/TOUCH0/HSPI_HD_G4") (pintype "bidirectional"))
      (node (ref "X2") (pin "9") (pinfunction "S_9") (pintype "passive"))
    )
    (net (code "73") (name "/RX") (class "Default")
      (node (ref "SJ7") (pin "2") (pinfunction "2_2") (pintype "passive"))
      (node (ref "SV1") (pin "6") (pinfunction "6_6") (pintype "passive"))
    )
    (net (code "74") (name "/RX2") (class "Default")
      (node (ref "SJ7") (pin "3") (pinfunction "3_3") (pintype "passive"))
      (node (ref "SJ8") (pin "3") (pinfunction "3_3") (pintype "passive"))
      (node (ref "U2") (pin "G16") (pinfunction "GPIO16/RX2_G16") (pintype "input"))
    )
    (net (code "75") (name "/S0-3") (class "Default")
      (node (ref "OK2") (pin "4") (pinfunction "COL_4") (pintype "passive"))
      (node (ref "R43") (pin "1") (pinfunction "1_1") (pintype "passive"))
      (node (ref "U2") (pin "G14") (pinfunction "GPIO14/ADC2_6/TOUCH6/HSPI_CLK_G14") (pintype "bidirectional"))
      (node (ref "X1") (pin "20") (pinfunction "S_20") (pintype "passive"))
    )
    (net (code "76") (name "/S0-4") (class "Default")
      (node (ref "OK1") (pin "4") (pinfunction "COL_4") (pintype "passive"))
      (node (ref "R44") (pin "1") (pinfunction "1_1") (pintype "passive"))
      (node (ref "U2") (pin "G15") (pinfunction "GPIO15/ADC2_3/TOUCH3/HSPI_CS0_G15") (pintype "bidirectional"))
      (node (ref "X1") (pin "18") (pinfunction "S_18") (pintype "passive"))
    )
    (net (code "77") (name "/SCL") (class "Default")
      (node (ref "IC7") (pin "7") (pinfunction "SY_7") (pintype "input"))
      (node (ref "IC8") (pin "12") (pinfunction "SCL_12") (pintype "input"))
      (node (ref "IC9") (pin "12") (pinfunction "SCL_12") (pintype "input"))
      (node (ref "R45") (pin "1") (pinfunction "1_1") (pintype "passive"))
      (node (ref "U2") (pin "G32") (pinfunction "GPIO32/ADC1_4/TOUCH9_G32") (pintype "bidirectional"))
      (node (ref "X2") (pin "7") (pinfunction "S_7") (pintype "passive"))
    )
    (net (code "78") (name "/SCL_X") (class "Default")
      (node (ref "CON2") (pin "3") (pinfunction "3_3") (pintype "passive"))
      (node (ref "D4") (pin "1") (pinfunction "K1_1") (pintype "passive"))
      (node (ref "IC7") (pin "5") (pinfunction "TY_5") (pintype "open_collector"))
      (node (ref "IC7") (pin "6") (pinfunction "RY_6") (pintype "open_collector"))
      (node (ref "R48") (pin "1") (pinfunction "1_1") (pintype "passive"))
    )
    (net (code "79") (name "/SDA") (class "Default")
      (node (ref "IC7") (pin "1") (pinfunction "SX_1") (pintype "input"))
      (node (ref "IC8") (pin "13") (pinfunction "SDA_13") (pintype "bidirectional"))
      (node (ref "IC9") (pin "13") (pinfunction "SDA_13") (pintype "bidirectional"))
      (node (ref "R47") (pin "1") (pinfunction "1_1") (pintype "passive"))
      (node (ref "U2") (pin "G33") (pinfunction "GPIO33/ADC1_5/TOUCH8_G33") (pintype "bidirectional"))
      (node (ref "X2") (pin "5") (pinfunction "S_5") (pintype "passive"))
    )
    (net (code "80") (name "/SDA_X") (class "Default")
      (node (ref "CON2") (pin "2") (pinfunction "2_2") (pintype "passive"))
      (node (ref "D4") (pin "2") (pinfunction "K2_2") (pintype "passive"))
      (node (ref "IC7") (pin "2") (pinfunction "RX_2") (pintype "open_collector"))
      (node (ref "IC7") (pin "3") (pinfunction "TX_3") (pintype "open_collector"))
      (node (ref "R49") (pin "1") (pinfunction "1_1") (pintype "passive"))
    )
    (net (code "81") (name "/TEMP1") (class "Default")
      (node (ref "R11") (pin "2") (pinfunction "2_2") (pintype "passive"))
      (node (ref "U2") (pin "G13") (pinfunction "GPIO13/ADC2_4/TOUCH4/HSPI_ID_G13") (pintype "bidirectional"))
    )
    (net (code "82") (name "/TX") (class "Default")
      (node (ref "SJ8") (pin "2") (pinfunction "2_2") (pintype "passive"))
      (node (ref "SV1") (pin "7") (pinfunction "7_7") (pintype "passive"))
    )
    (net (code "83") (name "/TX2") (class "Default")
      (node (ref "SJ7") (pin "1") (pinfunction "1_1") (pintype "passive"))
      (node (ref "SJ8") (pin "1") (pinfunction "1_1") (pintype "passive"))
      (node (ref "U2") (pin "G17") (pinfunction "GPIO17/TX2_G17") (pintype "output"))
    )
    (net (code "84") (name "/VCC") (class "Default")
      (node (ref "CON1") (pin "12") (pinfunction "12_12") (pintype "passive"))
      (node (ref "D1") (pin "A") (pinfunction "A_A") (pintype "passive"))
    )
    (net (code "85") (name "GND") (class "Default")
      (node (ref "C1") (pin "-") (pinfunction "-_-") (pintype "passive"))
      (node (ref "C3") (pin "-") (pinfunction "-_-") (pintype "passive"))
      (node (ref "C4") (pin "-") (pinfunction "-_-") (pintype "passive"))
      (node (ref "C5") (pin "2") (pinfunction "2_2") (pintype "passive"))
      (node (ref "C6") (pin "2") (pinfunction "2_2") (pintype "passive"))
      (node (ref "C7") (pin "2") (pinfunction "2_2") (pintype "passive"))
      (node (ref "C8") (pin "-") (pinfunction "-_-") (pintype "passive"))
      (node (ref "CON1") (pin "11") (pinfunction "11_11") (pintype "passive"))
      (node (ref "CON2") (pin "4") (pinfunction "4_4") (pintype "passive"))
      (node (ref "CON3") (pin "3") (pinfunction "3_3") (pintype "passive"))
      (node (ref "D4") (pin "3") (pinfunction "AA_3") (pintype "passive"))
      (node (ref "IC3") (pin "11") (pinfunction "EMIT3_11") (pintype "passive"))
      (node (ref "IC3") (pin "13") (pinfunction "EMIT2_13") (pintype "passive"))
      (node (ref "IC3") (pin "15") (pinfunction "EMIT1_15") (pintype "passive"))
      (node (ref "IC3") (pin "9") (pinfunction "EMIT4_9") (pintype "passive"))
      (node (ref "IC4") (pin "11") (pinfunction "EMIT3_11") (pintype "passive"))
      (node (ref "IC4") (pin "13") (pinfunction "EMIT2_13") (pintype "passive"))
      (node (ref "IC4") (pin "15") (pinfunction "EMIT1_15") (pintype "passive"))
      (node (ref "IC4") (pin "9") (pinfunction "EMIT4_9") (pintype "passive"))
      (node (ref "IC5") (pin "11") (pinfunction "EMIT3_11") (pintype "passive"))
      (node (ref "IC5") (pin "13") (pinfunction "EMIT2_13") (pintype "passive"))
      (node (ref "IC5") (pin "15") (pinfunction "EMIT1_15") (pintype "passive"))
      (node (ref "IC5") (pin "9") (pinfunction "EMIT4_9") (pintype "passive"))
      (node (ref "IC6") (pin "11") (pinfunction "EMIT3_11") (pintype "passive"))
      (node (ref "IC6") (pin "13") (pinfunction "EMIT2_13") (pintype "passive"))
      (node (ref "IC6") (pin "15") (pinfunction "EMIT1_15") (pintype "passive"))
      (node (ref "IC6") (pin "9") (pinfunction "EMIT4_9") (pintype "passive"))
      (node (ref "IC7") (pin "4") (pinfunction "GND_4") (pintype "power_in"))
      (node (ref "IC8") (pin "10") (pinfunction "VSS_10") (pintype "power_in"))
      (node (ref "IC9") (pin "10") (pinfunction "VSS_10") (pintype "power_in"))
      (node (ref "J1") (pin "3") (pinfunction "3_3") (pintype "passive"))
      (node (ref "J1") (pin "4") (pinfunction "4_4") (pintype "passive"))
      (node (ref "OK1") (pin "3") (pinfunction "EMIT_3") (pintype "passive"))
      (node (ref "OK2") (pin "3") (pinfunction "EMIT_3") (pintype "passive"))
      (node (ref "Q1") (pin "1") (pinfunction "GND_1") (pintype "power_in"))
      (node (ref "Q1") (pin "3") (pinfunction "GND_3") (pintype "power_in"))
      (node (ref "Q2") (pin "1") (pinfunction "GND_1") (pintype "power_in"))
      (node (ref "Q2") (pin "3") (pinfunction "GND_3") (pintype "power_in"))
      (node (ref "Q3") (pin "1") (pinfunction "GND_1") (pintype "power_in"))
      (node (ref "Q3") (pin "3") (pinfunction "GND_3") (pintype "power_in"))
      (node (ref "Q4") (pin "1") (pinfunction "GND_1") (pintype "power_in"))
      (node (ref "Q4") (pin "3") (pinfunction "GND_3") (pintype "power_in"))
      (node (ref "Q5") (pin "1") (pinfunction "GND_1") (pintype "power_in"))
      (node (ref "Q5") (pin "3") (pinfunction "GND_3") (pintype "power_in"))
      (node (ref "Q6") (pin "1") (pinfunction "GND_1") (pintype "power_in"))
      (node (ref "Q6") (pin "3") (pinfunction "GND_3") (pintype "power_in"))
      (node (ref "Q7") (pin "1") (pinfunction "GND_1") (pintype "power_in"))
      (node (ref "Q7") (pin "3") (pinfunction "GND_3") (pintype "power_in"))
      (node (ref "Q8") (pin "1") (pinfunction "GND_1") (pintype "power_in"))
      (node (ref "Q8") (pin "3") (pinfunction "GND_3") (pintype "power_in"))
      (node (ref "Q9") (pin "1") (pinfunction "GND_1") (pintype "power_in"))
      (node (ref "Q9") (pin "3") (pinfunction "GND_3") (pintype "power_in"))
      (node (ref "R23") (pin "1") (pinfunction "1_1") (pintype "passive"))
      (node (ref "R24") (pin "1") (pinfunction "1_1") (pintype "passive"))
      (node (ref "R25") (pin "1") (pinfunction "1_1") (pintype "passive"))
      (node (ref "R26") (pin "1") (pinfunction "1_1") (pintype "passive"))
      (node (ref "R27") (pin "1") (pinfunction "1_1") (pintype "passive"))
      (node (ref "R28") (pin "1") (pinfunction "1_1") (pintype "passive"))
      (node (ref "R29") (pin "1") (pinfunction "1_1") (pintype "passive"))
      (node (ref "R30") (pin "1") (pinfunction "1_1") (pintype "passive"))
      (node (ref "R31") (pin "1") (pinfunction "1_1") (pintype "passive"))
      (node (ref "R32") (pin "1") (pinfunction "1_1") (pintype "passive"))
      (node (ref "R33") (pin "1") (pinfunction "1_1") (pintype "passive"))
      (node (ref "R34") (pin "1") (pinfunction "1_1") (pintype "passive"))
      (node (ref "R35") (pin "1") (pinfunction "1_1") (pintype "passive"))
      (node (ref "R36") (pin "1") (pinfunction "1_1") (pintype "passive"))
      (node (ref "R37") (pin "1") (pinfunction "1_1") (pintype "passive"))
      (node (ref "R38") (pin "1") (pinfunction "1_1") (pintype "passive"))
      (node (ref "R39") (pin "1") (pinfunction "1_1") (pintype "passive"))
      (node (ref "R40") (pin "1") (pinfunction "1_1") (pintype "passive"))
      (node (ref "R51") (pin "1") (pinfunction "1_1") (pintype "passive"))
      (node (ref "SJ1") (pin "1") (pinfunction "1_1") (pintype "passive"))
      (node (ref "SJ2") (pin "1") (pinfunction "1_1") (pintype "passive"))
      (node (ref "SJ3") (pin "1") (pinfunction "1_1") (pintype "passive"))
      (node (ref "SJ4") (pin "1") (pinfunction "1_1") (pintype "passive"))
      (node (ref "SJ5") (pin "1") (pinfunction "1_1") (pintype "passive"))
      (node (ref "SJ6") (pin "1") (pinfunction "1_1") (pintype "passive"))
      (node (ref "SV1") (pin "1") (pinfunction "1_1") (pintype "passive"))
      (node (ref "SV1") (pin "5") (pinfunction "5_5") (pintype "passive"))
      (node (ref "U1") (pin "1") (pinfunction "GND_1") (pintype "input"))
      (node (ref "U2") (pin "GND@2") (pinfunction "GND_GND@2") (pintype "power_in"))
      (node (ref "U2") (pin "GND@3") (pinfunction "GND_GND@3") (pintype "power_in"))
      (node (ref "U3") (pin "GND") (pinfunction "GND_GND") (pintype "power_in"))
      (node (ref "U3") (pin "GND@1") (pinfunction "GND_GND@1") (pintype "power_in"))
      (node (ref "X1") (pin "17") (pinfunction "S_17") (pintype "passive"))
      (node (ref "X2") (pin "1") (pinfunction "S_1") (pintype "passive"))
    )
    (net (code "86") (name "Net-(CON1-Pad1)") (class "Default")
      (node (ref "CON1") (pin "1") (pinfunction "1_1") (pintype "passive"))
      (node (ref "Q1") (pin "5") (pinfunction "OUT_5") (pintype "output"))
      (node (ref "Q1") (pin "6") (pinfunction "OUT_6") (pintype "output"))
    )
    (net (code "87") (name "Net-(CON1-Pad2)") (class "Default")
      (node (ref "CON1") (pin "2") (pinfunction "2_2") (pintype "passive"))
      (node (ref "Q1") (pin "7") (pinfunction "OUT_7") (pintype "output"))
      (node (ref "Q1") (pin "8") (pinfunction "OUT_8") (pintype "output"))
    )
    (net (code "88") (name "Net-(CON1-Pad3)") (class "Default")
      (node (ref "CON1") (pin "3") (pinfunction "3_3") (pintype "passive"))
      (node (ref "Q2") (pin "5") (pinfunction "OUT_5") (pintype "output"))
      (node (ref "Q2") (pin "6") (pinfunction "OUT_6") (pintype "output"))
    )
    (net (code "89") (name "Net-(CON1-Pad4)") (class "Default")
      (node (ref "CON1") (pin "4") (pinfunction "4_4") (pintype "passive"))
      (node (ref "Q2") (pin "7") (pinfunction "OUT_7") (pintype "output"))
      (node (ref "Q2") (pin "8") (pinfunction "OUT_8") (pintype "output"))
    )
    (net (code "90") (name "Net-(CON1-Pad5)") (class "Default")
      (node (ref "CON1") (pin "5") (pinfunction "5_5") (pintype "passive"))
      (node (ref "Q3") (pin "5") (pinfunction "OUT_5") (pintype "output"))
      (node (ref "Q3") (pin "6") (pinfunction "OUT_6") (pintype "output"))
    )
    (net (code "91") (name "Net-(CON1-Pad6)") (class "Default")
      (node (ref "CON1") (pin "6") (pinfunction "6_6") (pintype "passive"))
      (node (ref "Q3") (pin "7") (pinfunction "OUT_7") (pintype "output"))
      (node (ref "Q3") (pin "8") (pinfunction "OUT_8") (pintype "output"))
    )
    (net (code "92") (name "Net-(CON1-Pad7)") (class "Default")
      (node (ref "CON1") (pin "7") (pinfunction "7_7") (pintype "passive"))
      (node (ref "Q4") (pin "5") (pinfunction "OUT_5") (pintype "output"))
      (node (ref "Q4") (pin "6") (pinfunction "OUT_6") (pintype "output"))
    )
    (net (code "93") (name "Net-(CON1-Pad8)") (class "Default")
      (node (ref "CON1") (pin "8") (pinfunction "8_8") (pintype "passive"))
      (node (ref "Q4") (pin "7") (pinfunction "OUT_7") (pintype "output"))
      (node (ref "Q4") (pin "8") (pinfunction "OUT_8") (pintype "output"))
    )
    (net (code "94") (name "Net-(CON2-Pad5)") (class "Default")
      (node (ref "CON2") (pin "5") (pinfunction "5_5") (pintype "passive"))
      (node (ref "Q6") (pin "5") (pinfunction "OUT_5") (pintype "output"))
      (node (ref "Q6") (pin "6") (pinfunction "OUT_6") (pintype "output"))
    )
    (net (code "95") (name "Net-(CON2-Pad6)") (class "Default")
      (node (ref "CON2") (pin "6") (pinfunction "6_6") (pintype "passive"))
      (node (ref "Q6") (pin "7") (pinfunction "OUT_7") (pintype "output"))
      (node (ref "Q6") (pin "8") (pinfunction "OUT_8") (pintype "output"))
    )
    (net (code "96") (name "Net-(CON2-Pad7)") (class "Default")
      (node (ref "CON2") (pin "7") (pinfunction "7_7") (pintype "passive"))
      (node (ref "Q7") (pin "5") (pinfunction "OUT_5") (pintype "output"))
      (node (ref "Q7") (pin "6") (pinfunction "OUT_6") (pintype "output"))
    )
    (net (code "97") (name "Net-(CON2-Pad8)") (class "Default")
      (node (ref "CON2") (pin "8") (pinfunction "8_8") (pintype "passive"))
      (node (ref "Q7") (pin "7") (pinfunction "OUT_7") (pintype "output"))
      (node (ref "Q7") (pin "8") (pinfunction "OUT_8") (pintype "output"))
    )
    (net (code "98") (name "Net-(CON2-Pad9)") (class "Default")
      (node (ref "CON2") (pin "9") (pinfunction "9_9") (pintype "passive"))
      (node (ref "Q8") (pin "5") (pinfunction "OUT_5") (pintype "output"))
      (node (ref "Q8") (pin "6") (pinfunction "OUT_6") (pintype "output"))
    )
    (net (code "99") (name "Net-(CON2-Pad10)") (class "Default")
      (node (ref "CON2") (pin "10") (pinfunction "10_10") (pintype "passive"))
      (node (ref "Q8") (pin "7") (pinfunction "OUT_7") (pintype "output"))
      (node (ref "Q8") (pin "8") (pinfunction "OUT_8") (pintype "output"))
    )
    (net (code "100") (name "Net-(CON2-Pad11)") (class "Default")
      (node (ref "CON2") (pin "11") (pinfunction "11_11") (pintype "passive"))
      (node (ref "Q9") (pin "5") (pinfunction "OUT_5") (pintype "output"))
      (node (ref "Q9") (pin "6") (pinfunction "OUT_6") (pintype "output"))
    )
    (net (code "101") (name "Net-(CON2-Pad12)") (class "Default")
      (node (ref "CON2") (pin "12") (pinfunction "12_12") (pintype "passive"))
      (node (ref "Q9") (pin "7") (pinfunction "OUT_7") (pintype "output"))
      (node (ref "Q9") (pin "8") (pinfunction "OUT_8") (pintype "output"))
    )
    (net (code "102") (name "Net-(CON3-Pad4)") (class "Default")
      (node (ref "CON3") (pin "4") (pinfunction "4_4") (pintype "passive"))
      (node (ref "R11") (pin "1") (pinfunction "1_1") (pintype "passive"))
      (node (ref "R21") (pin "1") (pinfunction "1_1") (pintype "passive"))
    )
    (net (code "103") (name "Net-(IC3-C1)") (class "Default")
      (node (ref "IC3") (pin "2") (pinfunction "C1_2") (pintype "passive"))
      (node (ref "R25") (pin "2") (pinfunction "2_2") (pintype "passive"))
    )
    (net (code "104") (name "Net-(IC3-C2)") (class "Default")
      (node (ref "IC3") (pin "4") (pinfunction "C2_4") (pintype "passive"))
      (node (ref "R26") (pin "2") (pinfunction "2_2") (pintype "passive"))
    )
    (net (code "105") (name "Net-(IC3-C3)") (class "Default")
      (node (ref "IC3") (pin "6") (pinfunction "C3_6") (pintype "passive"))
      (node (ref "R27") (pin "2") (pinfunction "2_2") (pintype "passive"))
    )
    (net (code "106") (name "Net-(IC3-C4)") (class "Default")
      (node (ref "IC3") (pin "8") (pinfunction "C4_8") (pintype "passive"))
      (node (ref "R28") (pin "2") (pinfunction "2_2") (pintype "passive"))
    )
    (net (code "107") (name "Net-(IC4-C1)") (class "Default")
      (node (ref "IC4") (pin "2") (pinfunction "C1_2") (pintype "passive"))
      (node (ref "R29") (pin "2") (pinfunction "2_2") (pintype "passive"))
    )
    (net (code "108") (name "Net-(IC4-C2)") (class "Default")
      (node (ref "IC4") (pin "4") (pinfunction "C2_4") (pintype "passive"))
      (node (ref "R30") (pin "2") (pinfunction "2_2") (pintype "passive"))
    )
    (net (code "109") (name "Net-(IC4-C3)") (class "Default")
      (node (ref "IC4") (pin "6") (pinfunction "C3_6") (pintype "passive"))
      (node (ref "R31") (pin "2") (pinfunction "2_2") (pintype "passive"))
    )
    (net (code "110") (name "Net-(IC4-C4)") (class "Default")
      (node (ref "IC4") (pin "8") (pinfunction "C4_8") (pintype "passive"))
      (node (ref "R32") (pin "2") (pinfunction "2_2") (pintype "passive"))
    )
    (net (code "111") (name "Net-(IC5-C1)") (class "Default")
      (node (ref "IC5") (pin "2") (pinfunction "C1_2") (pintype "passive"))
      (node (ref "R33") (pin "2") (pinfunction "2_2") (pintype "passive"))
    )
    (net (code "112") (name "Net-(IC5-C2)") (class "Default")
      (node (ref "IC5") (pin "4") (pinfunction "C2_4") (pintype "passive"))
      (node (ref "R34") (pin "2") (pinfunction "2_2") (pintype "passive"))
    )
    (net (code "113") (name "Net-(IC5-C3)") (class "Default")
      (node (ref "IC5") (pin "6") (pinfunction "C3_6") (pintype "passive"))
      (node (ref "R35") (pin "2") (pinfunction "2_2") (pintype "passive"))
    )
    (net (code "114") (name "Net-(IC5-C4)") (class "Default")
      (node (ref "IC5") (pin "8") (pinfunction "C4_8") (pintype "passive"))
      (node (ref "R36") (pin "2") (pinfunction "2_2") (pintype "passive"))
    )
    (net (code "115") (name "Net-(IC6-C1)") (class "Default")
      (node (ref "IC6") (pin "2") (pinfunction "C1_2") (pintype "passive"))
      (node (ref "R37") (pin "2") (pinfunction "2_2") (pintype "passive"))
    )
    (net (code "116") (name "Net-(IC6-C2)") (class "Default")
      (node (ref "IC6") (pin "4") (pinfunction "C2_4") (pintype "passive"))
      (node (ref "R38") (pin "2") (pinfunction "2_2") (pintype "passive"))
    )
    (net (code "117") (name "Net-(IC6-C3)") (class "Default")
      (node (ref "IC6") (pin "6") (pinfunction "C3_6") (pintype "passive"))
      (node (ref "R39") (pin "2") (pinfunction "2_2") (pintype "passive"))
    )
    (net (code "118") (name "Net-(IC6-C4)") (class "Default")
      (node (ref "IC6") (pin "8") (pinfunction "C4_8") (pintype "passive"))
      (node (ref "R40") (pin "2") (pinfunction "2_2") (pintype "passive"))
    )
    (net (code "119") (name "Net-(IC8-A0)") (class "Default")
      (node (ref "IC8") (pin "15") (pinfunction "A0_15") (pintype "input"))
      (node (ref "SJ3") (pin "2") (pinfunction "2_2") (pintype "passive"))
    )
    (net (code "120") (name "Net-(IC8-A1)") (class "Default")
      (node (ref "IC8") (pin "16") (pinfunction "A1_16") (pintype "input"))
      (node (ref "SJ2") (pin "2") (pinfunction "2_2") (pintype "passive"))
    )
    (net (code "121") (name "Net-(IC8-A2)") (class "Default")
      (node (ref "IC8") (pin "17") (pinfunction "A2_17") (pintype "input"))
      (node (ref "SJ1") (pin "2") (pinfunction "2_2") (pintype "passive"))
    )
    (net (code "122") (name "Net-(IC8-~{RESET})") (class "Default")
      (node (ref "IC8") (pin "18") (pinfunction "~{RESET}_18") (pintype "input"))
      (node (ref "R46") (pin "1") (pinfunction "1_1") (pintype "passive"))
    )
    (net (code "123") (name "Net-(IC9-A0)") (class "Default")
      (node (ref "IC9") (pin "15") (pinfunction "A0_15") (pintype "input"))
      (node (ref "SJ6") (pin "2") (pinfunction "2_2") (pintype "passive"))
    )
    (net (code "124") (name "Net-(IC9-A1)") (class "Default")
      (node (ref "IC9") (pin "16") (pinfunction "A1_16") (pintype "input"))
      (node (ref "SJ5") (pin "2") (pinfunction "2_2") (pintype "passive"))
    )
    (net (code "125") (name "Net-(IC9-A2)") (class "Default")
      (node (ref "IC9") (pin "17") (pinfunction "A2_17") (pintype "input"))
      (node (ref "SJ4") (pin "2") (pinfunction "2_2") (pintype "passive"))
    )
    (net (code "126") (name "Net-(IC9-~{RESET})") (class "Default")
      (node (ref "IC9") (pin "18") (pinfunction "~{RESET}_18") (pintype "input"))
      (node (ref "R52") (pin "1") (pinfunction "1_1") (pintype "passive"))
    )
    (net (code "127") (name "Net-(OK1-C)") (class "Default")
      (node (ref "OK1") (pin "2") (pinfunction "C_2") (pintype "passive"))
      (node (ref "R24") (pin "2") (pinfunction "2_2") (pintype "passive"))
    )
    (net (code "128") (name "Net-(OK2-C)") (class "Default")
      (node (ref "OK2") (pin "2") (pinfunction "C_2") (pintype "passive"))
      (node (ref "R23") (pin "2") (pinfunction "2_2") (pintype "passive"))
    )
    (net (code "129") (name "Net-(Q1A-IN)") (class "Default")
      (node (ref "Q1") (pin "2") (pinfunction "IN_2") (pintype "input"))
      (node (ref "R2") (pin "2") (pinfunction "2_2") (pintype "passive"))
    )
    (net (code "130") (name "Net-(Q1B-IN)") (class "Default")
      (node (ref "Q1") (pin "4") (pinfunction "IN_4") (pintype "input"))
      (node (ref "R1") (pin "2") (pinfunction "2_2") (pintype "passive"))
    )
    (net (code "131") (name "Net-(Q2A-IN)") (class "Default")
      (node (ref "Q2") (pin "2") (pinfunction "IN_2") (pintype "input"))
      (node (ref "R4") (pin "2") (pinfunction "2_2") (pintype "passive"))
    )
    (net (code "132") (name "Net-(Q2B-IN)") (class "Default")
      (node (ref "Q2") (pin "4") (pinfunction "IN_4") (pintype "input"))
      (node (ref "R3") (pin "2") (pinfunction "2_2") (pintype "passive"))
    )
    (net (code "133") (name "Net-(Q3A-IN)") (class "Default")
      (node (ref "Q3") (pin "2") (pinfunction "IN_2") (pintype "input"))
      (node (ref "R6") (pin "2") (pinfunction "2_2") (pintype "passive"))
    )
    (net (code "134") (name "Net-(Q3B-IN)") (class "Default")
      (node (ref "Q3") (pin "4") (pinfunction "IN_4") (pintype "input"))
      (node (ref "R5") (pin "2") (pinfunction "2_2") (pintype "passive"))
    )
    (net (code "135") (name "Net-(Q4A-IN)") (class "Default")
      (node (ref "Q4") (pin "2") (pinfunction "IN_2") (pintype "input"))
      (node (ref "R8") (pin "2") (pinfunction "2_2") (pintype "passive"))
    )
    (net (code "136") (name "Net-(Q4B-IN)") (class "Default")
      (node (ref "Q4") (pin "4") (pinfunction "IN_4") (pintype "input"))
      (node (ref "R7") (pin "2") (pinfunction "2_2") (pintype "passive"))
    )
    (net (code "137") (name "Net-(Q5A-IN)") (class "Default")
      (node (ref "Q5") (pin "2") (pinfunction "IN_2") (pintype "input"))
      (node (ref "R10") (pin "2") (pinfunction "2_2") (pintype "passive"))
    )
    (net (code "138") (name "Net-(Q5B-IN)") (class "Default")
      (node (ref "Q5") (pin "4") (pinfunction "IN_4") (pintype "input"))
      (node (ref "R9") (pin "2") (pinfunction "2_2") (pintype "passive"))
    )
    (net (code "139") (name "Net-(Q6A-IN)") (class "Default")
      (node (ref "Q6") (pin "2") (pinfunction "IN_2") (pintype "input"))
      (node (ref "R14") (pin "2") (pinfunction "2_2") (pintype "passive"))
    )
    (net (code "140") (name "Net-(Q6B-IN)") (class "Default")
      (node (ref "Q6") (pin "4") (pinfunction "IN_4") (pintype "input"))
      (node (ref "R13") (pin "2") (pinfunction "2_2") (pintype "passive"))
    )
    (net (code "141") (name "Net-(Q7A-IN)") (class "Default")
      (node (ref "Q7") (pin "2") (pinfunction "IN_2") (pintype "input"))
      (node (ref "R16") (pin "2") (pinfunction "2_2") (pintype "passive"))
    )
    (net (code "142") (name "Net-(Q7B-IN)") (class "Default")
      (node (ref "Q7") (pin "4") (pinfunction "IN_4") (pintype "input"))
      (node (ref "R15") (pin "2") (pinfunction "2_2") (pintype "passive"))
    )
    (net (code "143") (name "Net-(Q8A-IN)") (class "Default")
      (node (ref "Q8") (pin "2") (pinfunction "IN_2") (pintype "input"))
      (node (ref "R18") (pin "2") (pinfunction "2_2") (pintype "passive"))
    )
    (net (code "144") (name "Net-(Q8B-IN)") (class "Default")
      (node (ref "Q8") (pin "4") (pinfunction "IN_4") (pintype "input"))
      (node (ref "R17") (pin "2") (pinfunction "2_2") (pintype "passive"))
    )
    (net (code "145") (name "Net-(Q9A-IN)") (class "Default")
      (node (ref "Q9") (pin "2") (pinfunction "IN_2") (pintype "input"))
      (node (ref "R20") (pin "2") (pinfunction "2_2") (pintype "passive"))
    )
    (net (code "146") (name "Net-(Q9B-IN)") (class "Default")
      (node (ref "Q9") (pin "4") (pinfunction "IN_4") (pintype "input"))
      (node (ref "R19") (pin "2") (pinfunction "2_2") (pintype "passive"))
    )
    (net (code "147") (name "unconnected-(H1-MOUNT-PadB3,2)") (class "Default")
      (node (ref "H1") (pin "B3,2") (pinfunction "MOUNT_B3,2") (pintype "passive"))
    )
    (net (code "148") (name "unconnected-(H2-MOUNT-PadB3,2)") (class "Default")
      (node (ref "H2") (pin "B3,2") (pinfunction "MOUNT_B3,2") (pintype "passive"))
    )
    (net (code "149") (name "unconnected-(H3-MOUNT-PadB3,2)") (class "Default")
      (node (ref "H3") (pin "B3,2") (pinfunction "MOUNT_B3,2") (pintype "passive"))
    )
    (net (code "150") (name "unconnected-(H4-MOUNT-PadB3,2)") (class "Default")
      (node (ref "H4") (pin "B3,2") (pinfunction "MOUNT_B3,2") (pintype "passive"))
    )
    (net (code "151") (name "unconnected-(IC8-INTA-Pad20)") (class "Default")
      (node (ref "IC8") (pin "20") (pinfunction "INTA_20") (pintype "output"))
    )
    (net (code "152") (name "unconnected-(IC8-INTB-Pad19)") (class "Default")
      (node (ref "IC8") (pin "19") (pinfunction "INTB_19") (pintype "output"))
    )
    (net (code "153") (name "unconnected-(IC9-INTA-Pad20)") (class "Default")
      (node (ref "IC9") (pin "20") (pinfunction "INTA_20") (pintype "output"))
    )
    (net (code "154") (name "unconnected-(IC9-INTB-Pad19)") (class "Default")
      (node (ref "IC9") (pin "19") (pinfunction "INTB_19") (pintype "output"))
    )
    (net (code "155") (name "unconnected-(SV1-Pad4)") (class "Default")
      (node (ref "SV1") (pin "4") (pinfunction "4_4") (pintype "passive"))
    )
    (net (code "156") (name "unconnected-(U2-GPIO1{slash}TX0-PadTX0)") (class "Default")
      (node (ref "U2") (pin "TX0") (pinfunction "GPIO1/TX0_TX0") (pintype "output"))
    )
    (net (code "157") (name "unconnected-(U2-GPIO3{slash}RX0-PadRX0)") (class "Default")
      (node (ref "U2") (pin "RX0") (pinfunction "GPIO3/RX0_RX0") (pintype "input"))
    )
    (net (code "158") (name "unconnected-(U2-GPIO7{slash}SDO{slash}SD0{slash}~{}-PadSD0)") (class "Default")
      (node (ref "U2") (pin "SD0") (pinfunction "GPIO7/SDO/SD0/~{}_SD0") (pintype "bidirectional"))
    )
    (net (code "159") (name "unconnected-(U2-GPIO8{slash}SDI{slash}SD1{slash}~{}-PadSD1)") (class "Default")
      (node (ref "U2") (pin "SD1") (pinfunction "GPIO8/SDI/SD1/~{}_SD1") (pintype "bidirectional"))
    )
    (net (code "160") (name "unconnected-(U2-GPIO9{slash}SHD{slash}SD2{slash}~{}-PadSD2)") (class "Default")
      (node (ref "U2") (pin "SD2") (pinfunction "GPIO9/SHD/SD2/~{}_SD2") (pintype "bidirectional"))
    )
    (net (code "161") (name "unconnected-(U2-GPIO10{slash}SWP{slash}SD3{slash}~{}-PadSD3)") (class "Default")
      (node (ref "U2") (pin "SD3") (pinfunction "GPIO10/SWP/SD3/~{}_SD3") (pintype "bidirectional"))
    )
    (net (code "162") (name "unconnected-(U2-GPIO11{slash}CMD{slash}~{}-PadCMD)") (class "Default")
      (node (ref "U2") (pin "CMD") (pinfunction "GPIO11/CMD/~{}_CMD") (pintype "bidirectional"))
    )
    (net (code "163") (name "unconnected-(U2-GPIO34{slash}ADC1_4-PadG34)") (class "Default")
      (node (ref "U2") (pin "G34") (pinfunction "GPIO34/ADC1_4_G34") (pintype "bidirectional"))
    )
    (net (code "164") (name "unconnected-(U2-GPIO35{slash}ADC1_7-PadG35)") (class "Default")
      (node (ref "U2") (pin "G35") (pinfunction "GPIO35/ADC1_7_G35") (pintype "bidirectional"))
    )
    (net (code "165") (name "unconnected-(U2-PadEN)") (class "Default")
      (node (ref "U2") (pin "EN") (pinfunction "EN_EN") (pintype "input"))
    )
    (net (code "166") (name "unconnected-(U2-VN{slash}GPIO39{slash}ADC1_3-PadSN)") (class "Default")
      (node (ref "U2") (pin "SN") (pinfunction "VN/GPIO39/ADC1_3_SN") (pintype "bidirectional"))
    )
    (net (code "167") (name "unconnected-(U2-VP{slash}GPIO36{slash}ADC1_0-PadSP)") (class "Default")
      (node (ref "U2") (pin "SP") (pinfunction "VP/GPIO36/ADC1_0_SP") (pintype "bidirectional"))
    )
  )
)
